# Shunt_Board_V1_0.net
KiCad netlist of a schematic drawn in EAGLE
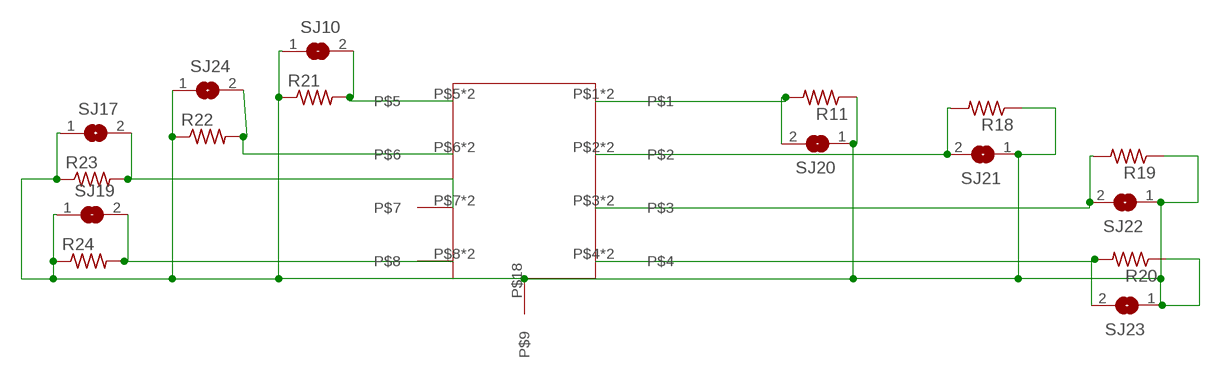
[diagram p0: schematic, sheet 1]

(export (version "E")
  (design (tool "Eeschema 10.0.6"))
  (components
    (comp (ref "R11")
      (value "R-US_0204/5")
      (footprint "eagle-import:0204_5")
      (libsource (lib "eagle-import") (part "R-US_0204/5"))
    )
    (comp (ref "R18")
      (value "R-US_0204/5")
      (footprint "eagle-import:0204_5")
      (libsource (lib "eagle-import") (part "R-US_0204/5"))
    )
    (comp (ref "R19")
      (value "R-US_0204/5")
      (footprint "eagle-import:0204_5")
      (libsource (lib "eagle-import") (part "R-US_0204/5"))
    )
    (comp (ref "R20")
      (value "R-US_0204/5")
      (footprint "eagle-import:0204_5")
      (libsource (lib "eagle-import") (part "R-US_0204/5"))
    )
    (comp (ref "R21")
      (value "R-US_0204/5")
      (footprint "eagle-import:0204_5")
      (libsource (lib "eagle-import") (part "R-US_0204/5"))
    )
    (comp (ref "R22")
      (value "R-US_0204/5")
      (footprint "eagle-import:0204_5")
      (libsource (lib "eagle-import") (part "R-US_0204/5"))
    )
    (comp (ref "R23")
      (value "R-US_0204/5")
      (footprint "eagle-import:0204_5")
      (libsource (lib "eagle-import") (part "R-US_0204/5"))
    )
    (comp (ref "R24")
      (value "R-US_0204/5")
      (footprint "eagle-import:0204_5")
      (libsource (lib "eagle-import") (part "R-US_0204/5"))
    )
    (comp (ref "SJ10")
      (value "SJ")
      (footprint "eagle-import:SJ")
      (libsource (lib "eagle-import") (part "SJ"))
    )
    (comp (ref "SJ17")
      (value "SJ")
      (footprint "eagle-import:SJ")
      (libsource (lib "eagle-import") (part "SJ"))
    )
    (comp (ref "SJ19")
      (value "SJ")
      (footprint "eagle-import:SJ")
      (libsource (lib "eagle-import") (part "SJ"))
    )
    (comp (ref "SJ20")
      (value "SJ")
      (footprint "eagle-import:SJ")
      (libsource (lib "eagle-import") (part "SJ"))
    )
    (comp (ref "SJ21")
      (value "SJ")
      (footprint "eagle-import:SJ")
      (libsource (lib "eagle-import") (part "SJ"))
    )
    (comp (ref "SJ22")
      (value "SJ")
      (footprint "eagle-import:SJ")
      (libsource (lib "eagle-import") (part "SJ"))
    )
    (comp (ref "SJ23")
      (value "SJ")
      (footprint "eagle-import:SJ")
      (libsource (lib "eagle-import") (part "SJ"))
    )
    (comp (ref "SJ24")
      (value "SJ")
      (footprint "eagle-import:SJ")
      (libsource (lib "eagle-import") (part "SJ"))
    )
    (comp (ref "U$28")
      (value "SHUNT2")
      (footprint "eagle-import:SHUNT2")
      (libsource (lib "eagle-import") (part "SHUNT2"))
    )
  )
  (nets
    (net (code "1") (name "Net-(R11-Pad2)") (class "Default")
      (node (ref "R11") (pin "2") (pinfunction "2_2") (pintype "passive"))
      (node (ref "SJ20") (pin "2") (pinfunction "2_2") (pintype "passive"))
      (node (ref "U$28") (pin "P$1") (pinfunction "P$1_P$1") (pintype "bidirectional"))
      (node (ref "U$28") (pin "P$10") (pinfunction "P$1_P$10") (pintype "bidirectional"))
    )
    (net (code "2") (name "Net-(R18-Pad2)") (class "Default")
      (node (ref "R18") (pin "2") (pinfunction "2_2") (pintype "passive"))
      (node (ref "SJ21") (pin "2") (pinfunction "2_2") (pintype "passive"))
      (node (ref "U$28") (pin "P$11") (pinfunction "P$2_P$11") (pintype "bidirectional"))
      (node (ref "U$28") (pin "P$2") (pinfunction "P$2_P$2") (pintype "bidirectional"))
    )
    (net (code "3") (name "Net-(R19-Pad2)") (class "Default")
      (node (ref "R19") (pin "2") (pinfunction "2_2") (pintype "passive"))
      (node (ref "SJ22") (pin "2") (pinfunction "2_2") (pintype "passive"))
      (node (ref "U$28") (pin "P$12") (pinfunction "P$3_P$12") (pintype "bidirectional"))
      (node (ref "U$28") (pin "P$3") (pinfunction "P$3_P$3") (pintype "bidirectional"))
    )
    (net (code "4") (name "Net-(R20-Pad2)") (class "Default")
      (node (ref "R20") (pin "2") (pinfunction "2_2") (pintype "passive"))
      (node (ref "SJ23") (pin "2") (pinfunction "2_2") (pintype "passive"))
      (node (ref "U$28") (pin "P$13") (pinfunction "P$4_P$13") (pintype "bidirectional"))
      (node (ref "U$28") (pin "P$4") (pinfunction "P$4_P$4") (pintype "bidirectional"))
    )
    (net (code "5") (name "Net-(R21-Pad2)") (class "Default")
      (node (ref "R21") (pin "2") (pinfunction "2_2") (pintype "passive"))
      (node (ref "SJ10") (pin "2") (pinfunction "2_2") (pintype "passive"))
      (node (ref "U$28") (pin "P$14") (pinfunction "P$5_P$14") (pintype "bidirectional"))
      (node (ref "U$28") (pin "P$5") (pinfunction "P$5_P$5") (pintype "bidirectional"))
    )
    (net (code "6") (name "Net-(R22-Pad2)") (class "Default")
      (node (ref "R22") (pin "2") (pinfunction "2_2") (pintype "passive"))
      (node (ref "SJ24") (pin "2") (pinfunction "2_2") (pintype "passive"))
      (node (ref "U$28") (pin "P$15") (pinfunction "P$6_P$15") (pintype "bidirectional"))
      (node (ref "U$28") (pin "P$6") (pinfunction "P$6_P$6") (pintype "bidirectional"))
    )
    (net (code "7") (name "Net-(R23-Pad2)") (class "Default")
      (node (ref "R23") (pin "2") (pinfunction "2_2") (pintype "passive"))
      (node (ref "SJ17") (pin "2") (pinfunction "2_2") (pintype "passive"))
      (node (ref "U$28") (pin "P$16") (pinfunction "P$7_P$16") (pintype "bidirectional"))
      (node (ref "U$28") (pin "P$7") (pinfunction "P$7_P$7") (pintype "bidirectional"))
    )
    (net (code "8") (name "Net-(R24-Pad2)") (class "Default")
      (node (ref "R24") (pin "2") (pinfunction "2_2") (pintype "passive"))
      (node (ref "SJ19") (pin "2") (pinfunction "2_2") (pintype "passive"))
      (node (ref "U$28") (pin "P$17") (pinfunction "P$8_P$17") (pintype "bidirectional"))
      (node (ref "U$28") (pin "P$8") (pinfunction "P$8_P$8") (pintype "bidirectional"))
    )
    (net (code "9") (name "Net-(U$28-P$9)") (class "Default")
      (node (ref "R11") (pin "1") (pinfunction "1_1") (pintype "passive"))
      (node (ref "R18") (pin "1") (pinfunction "1_1") (pintype "passive"))
      (node (ref "R19") (pin "1") (pinfunction "1_1") (pintype "passive"))
      (node (ref "R20") (pin "1") (pinfunction "1_1") (pintype "passive"))
      (node (ref "R21") (pin "1") (pinfunction "1_1") (pintype "passive"))
      (node (ref "R22") (pin "1") (pinfunction "1_1") (pintype "passive"))
      (node (ref "R23") (pin "1") (pinfunction "1_1") (pintype "passive"))
      (node (ref "R24") (pin "1") (pinfunction "1_1") (pintype "passive"))
      (node (ref "SJ10") (pin "1") (pinfunction "1_1") (pintype "passive"))
      (node (ref "SJ17") (pin "1") (pinfunction "1_1") (pintype "passive"))
      (node (ref "SJ19") (pin "1") (pinfunction "1_1") (pintype "passive"))
      (node (ref "SJ20") (pin "1") (pinfunction "1_1") (pintype "passive"))
      (node (ref "SJ21") (pin "1") (pinfunction "1_1") (pintype "passive"))
      (node (ref "SJ22") (pin "1") (pinfunction "1_1") (pintype "passive"))
      (node (ref "SJ23") (pin "1") (pinfunction "1_1") (pintype "passive"))
      (node (ref "SJ24") (pin "1") (pinfunction "1_1") (pintype "passive"))
      (node (ref "U$28") (pin "P$18") (pinfunction "P$9_P$18") (pintype "bidirectional"))
    )
  )
)
